# PJ_GRA_F.net
KiCad netlist of a schematic drawn in Altium Designer
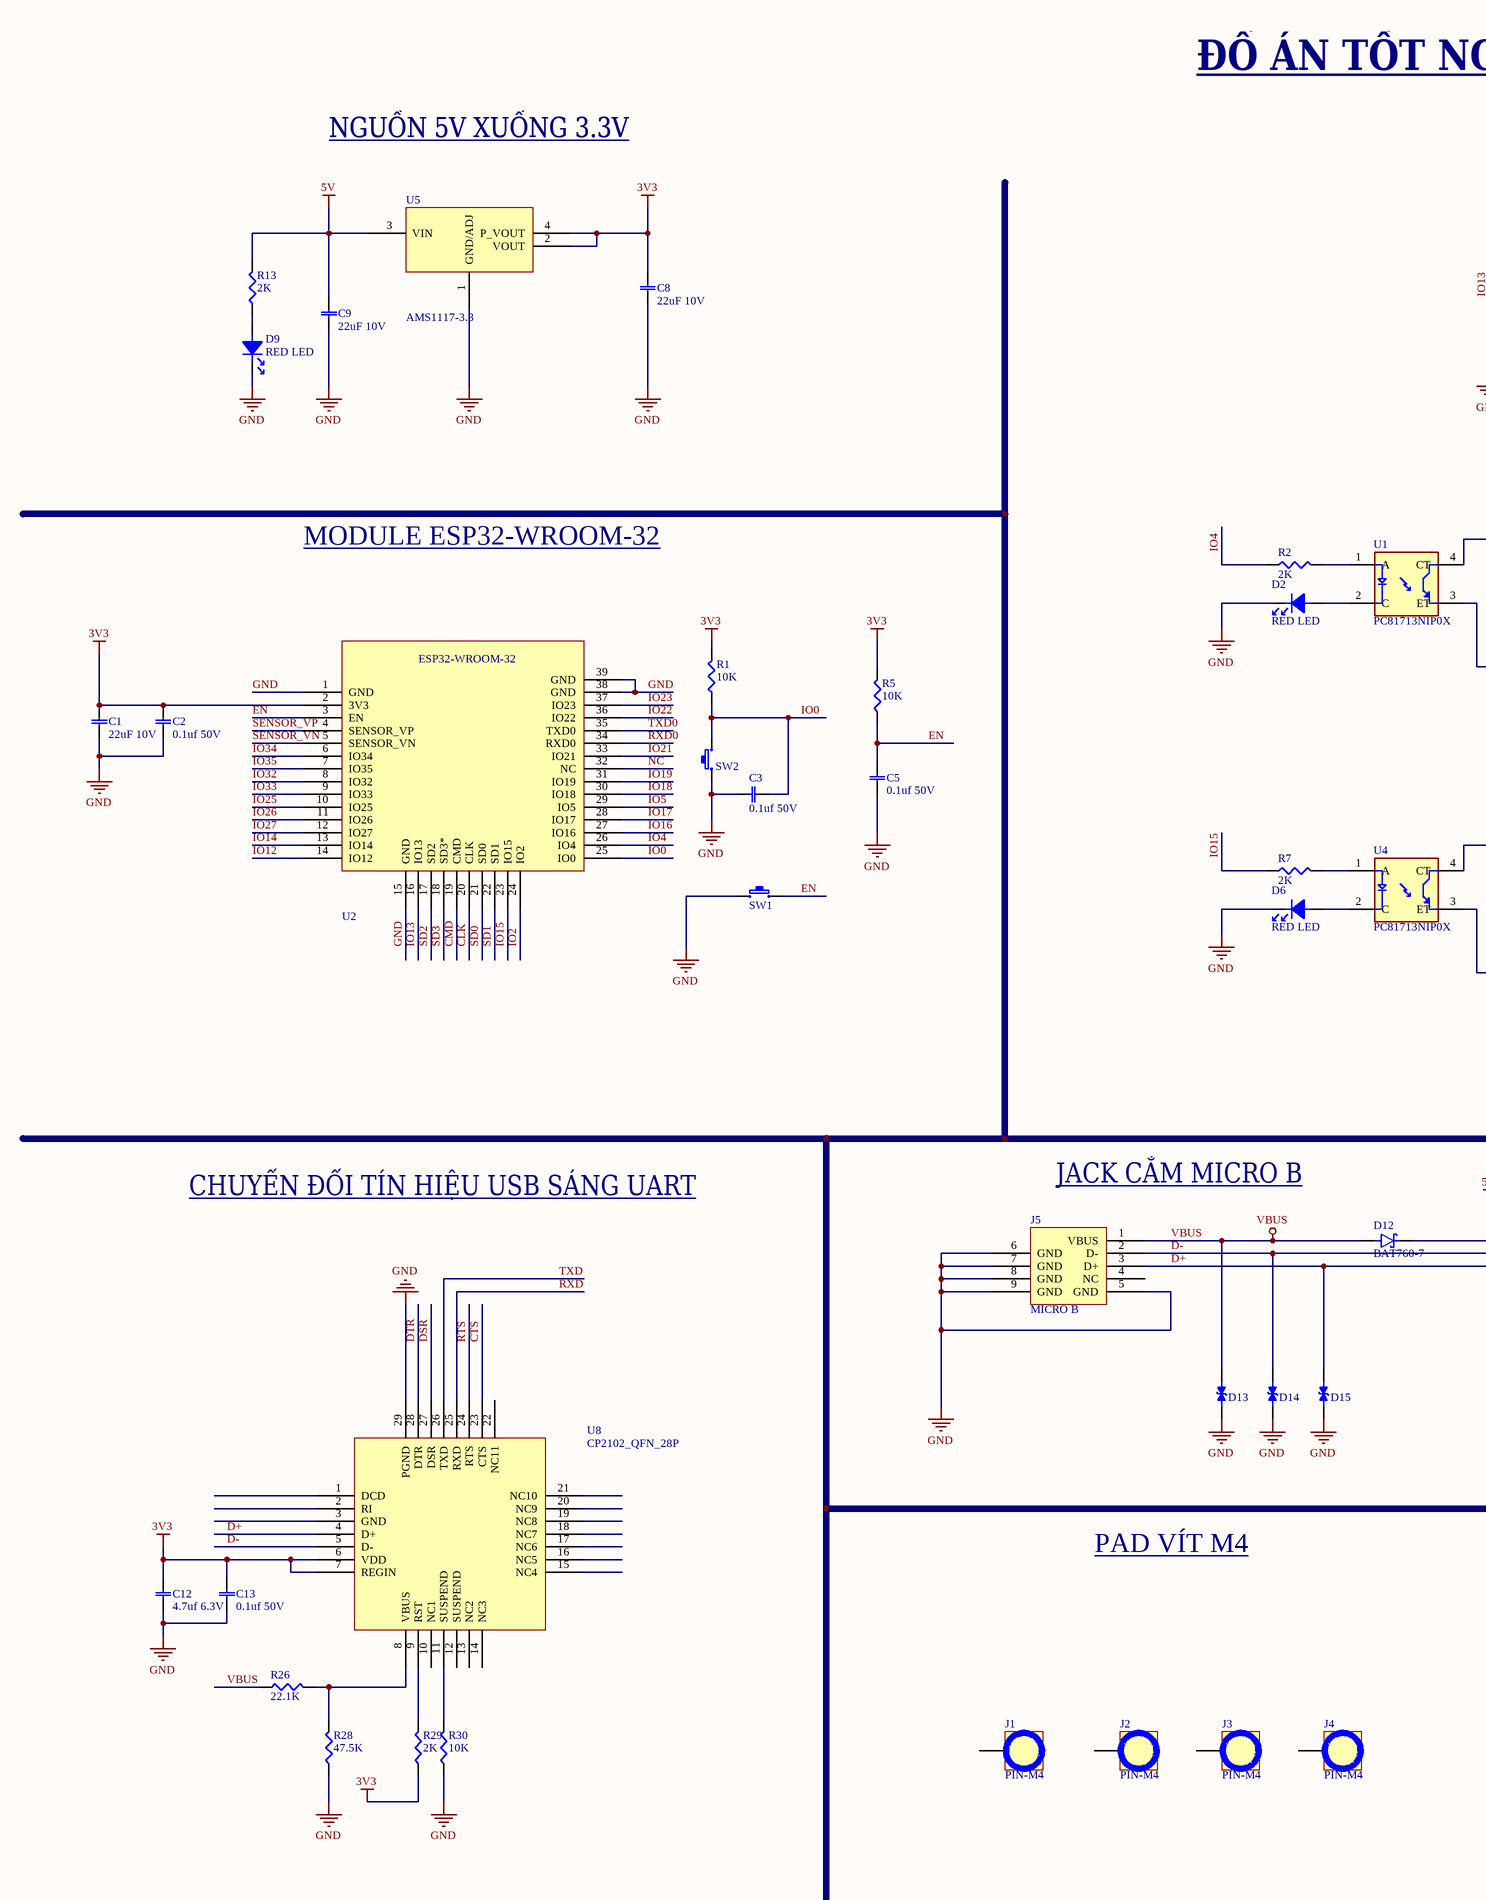
[diagram p0: PJ_GRA_F.SchDoc, left]
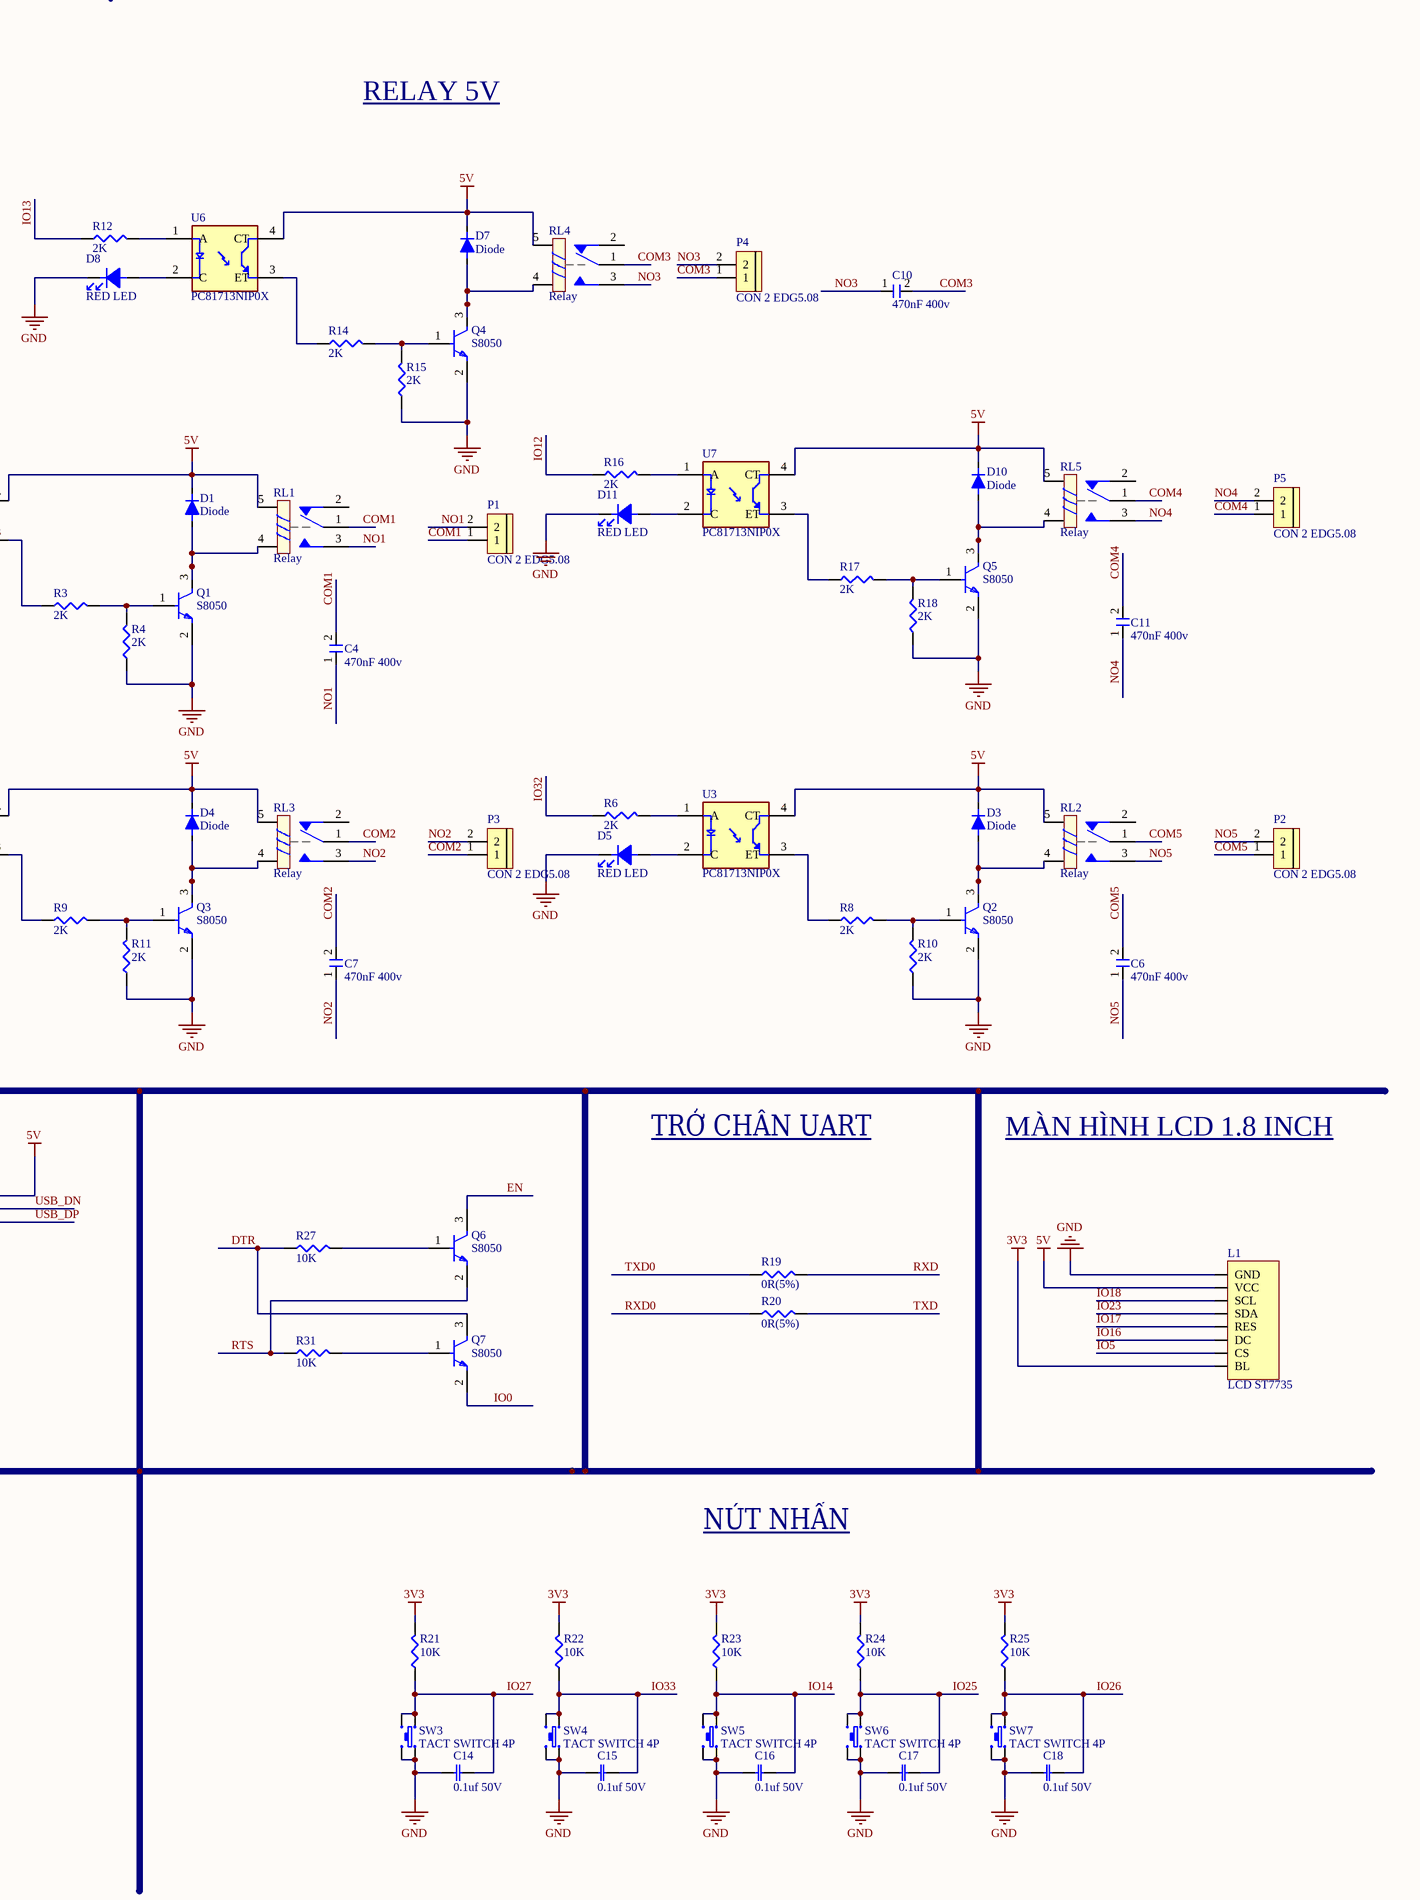
[diagram p1: PJ_GRA_F.SchDoc, right]

(export (version "E")
  (design (tool "Eeschema 10.0.6"))
  (components
    (comp (ref "C1")
      (value "22uF 10V")
      (footprint "FP-GRM188-0_2-IPC_A")
      (description "CAP CER 22UF 6.3V X5R 0603")
      (fields
        (field (name "MANUFACTURER") "Murata")
        (field (name "MANUFACTURER PART NUMBER") "GRM188R60J226MEA0J")
      )
      (libsource (lib "PJ_GRA_F") (part "GRM188R60J226MEA0J"))
    )
    (comp (ref "C2")
      (value "0.1uf 50V")
      (footprint "FP-C1005-050-0_05-IPC_A")
      (description "CAP CER 0.1UF 50V X7R 0402")
      (fields
        (field (name "MANUFACTURER") "TDK")
        (field (name "MANUFACTURER PART NUMBER") "C1005X7R1H104K050BB")
      )
      (libsource (lib "PJ_GRA_F") (part "C1005X7R1H104K050BB"))
    )
    (comp (ref "C3")
      (value "0.1uf 50V")
      (footprint "FP-C1005-050-0_05-IPC_A")
      (description "CAP CER 0.1UF 50V X7R 0402")
      (fields
        (field (name "MANUFACTURER") "TDK")
        (field (name "MANUFACTURER PART NUMBER") "C1005X7R1H104K050BB")
      )
      (libsource (lib "PJ_GRA_F") (part "C1005X7R1H104K050BB"))
    )
    (comp (ref "C4")
      (value "470nF 400v")
      (footprint "CAPRR750W80L1900T780H2200")
      (description "CAP 470nF 400V TH")
      (fields (field (name "MP") "ECQE4474RJT"))
      (libsource (lib "PJ_GRA_F") (part "470NF"))
    )
    (comp (ref "C5")
      (value "0.1uf 50V")
      (footprint "FP-C1005-050-0_05-IPC_A")
      (description "CAP CER 0.1UF 50V X7R 0402")
      (fields
        (field (name "MANUFACTURER") "TDK")
        (field (name "MANUFACTURER PART NUMBER") "C1005X7R1H104K050BB")
      )
      (libsource (lib "PJ_GRA_F") (part "C1005X7R1H104K050BB"))
    )
    (comp (ref "C6")
      (value "470nF 400v")
      (footprint "CAPRR750W80L1900T780H2200")
      (description "CAP 470nF 400V TH")
      (fields (field (name "MP") "ECQE4474RJT"))
      (libsource (lib "PJ_GRA_F") (part "470NF"))
    )
    (comp (ref "C7")
      (value "470nF 400v")
      (footprint "CAPRR750W80L1900T780H2200")
      (description "CAP 470nF 400V TH")
      (fields (field (name "MP") "ECQE4474RJT"))
      (libsource (lib "PJ_GRA_F") (part "470NF"))
    )
    (comp (ref "C8")
      (value "22uF 10V")
      (footprint "FP-GRM188-0_2-IPC_A")
      (description "CAP CER 22UF 6.3V X5R 0603")
      (fields
        (field (name "MANUFACTURER") "Murata")
        (field (name "MANUFACTURER PART NUMBER") "GRM188R60J226MEA0J")
      )
      (libsource (lib "PJ_GRA_F") (part "GRM188R60J226MEA0J"))
    )
    (comp (ref "C9")
      (value "22uF 10V")
      (footprint "FP-GRM188-0_2-IPC_A")
      (description "CAP CER 22UF 6.3V X5R 0603")
      (fields
        (field (name "MANUFACTURER") "Murata")
        (field (name "MANUFACTURER PART NUMBER") "GRM188R60J226MEA0J")
      )
      (libsource (lib "PJ_GRA_F") (part "GRM188R60J226MEA0J"))
    )
    (comp (ref "C10")
      (value "470nF 400v")
      (footprint "CAPRR750W80L1900T780H2200")
      (description "CAP 470nF 400V TH")
      (fields (field (name "MP") "ECQE4474RJT"))
      (libsource (lib "PJ_GRA_F") (part "470NF"))
    )
    (comp (ref "C11")
      (value "470nF 400v")
      (footprint "CAPRR750W80L1900T780H2200")
      (description "CAP 470nF 400V TH")
      (fields (field (name "MP") "ECQE4474RJT"))
      (libsource (lib "PJ_GRA_F") (part "470NF"))
    )
    (comp (ref "C12")
      (value "4.7uf 6.3V")
      (footprint "FP-C1005-050-0_05-IPC_A")
      (description "CAP CER 4.7UF 6.3V X5R 0402")
      (fields
        (field (name "MANUFACTURER") "Samsung")
        (field (name "MANUFACTURER PART NUMBER") "CL05A475KQ5NRNC")
      )
      (libsource (lib "PJ_GRA_F") (part "CL05A475KQ5NRNC"))
    )
    (comp (ref "C13")
      (value "0.1uf 50V")
      (footprint "FP-C1005-050-0_05-IPC_A")
      (description "CAP CER 0.1UF 50V X7R 0402")
      (fields
        (field (name "MANUFACTURER") "TDK")
        (field (name "MANUFACTURER PART NUMBER") "C1005X7R1H104K050BB")
      )
      (libsource (lib "PJ_GRA_F") (part "C1005X7R1H104K050BB"))
    )
    (comp (ref "C14")
      (value "0.1uf 50V")
      (footprint "FP-C1005-050-0_05-IPC_A")
      (description "CAP CER 0.1UF 50V X7R 0402")
      (fields
        (field (name "MANUFACTURER") "TDK")
        (field (name "MANUFACTURER PART NUMBER") "C1005X7R1H104K050BB")
      )
      (libsource (lib "PJ_GRA_F") (part "C1005X7R1H104K050BB"))
    )
    (comp (ref "C15")
      (value "0.1uf 50V")
      (footprint "FP-C1005-050-0_05-IPC_A")
      (description "CAP CER 0.1UF 50V X7R 0402")
      (fields
        (field (name "MANUFACTURER") "TDK")
        (field (name "MANUFACTURER PART NUMBER") "C1005X7R1H104K050BB")
      )
      (libsource (lib "PJ_GRA_F") (part "C1005X7R1H104K050BB"))
    )
    (comp (ref "C16")
      (value "0.1uf 50V")
      (footprint "FP-C1005-050-0_05-IPC_A")
      (description "CAP CER 0.1UF 50V X7R 0402")
      (fields
        (field (name "MANUFACTURER") "TDK")
        (field (name "MANUFACTURER PART NUMBER") "C1005X7R1H104K050BB")
      )
      (libsource (lib "PJ_GRA_F") (part "C1005X7R1H104K050BB"))
    )
    (comp (ref "C17")
      (value "0.1uf 50V")
      (footprint "FP-C1005-050-0_05-IPC_A")
      (description "CAP CER 0.1UF 50V X7R 0402")
      (fields
        (field (name "MANUFACTURER") "TDK")
        (field (name "MANUFACTURER PART NUMBER") "C1005X7R1H104K050BB")
      )
      (libsource (lib "PJ_GRA_F") (part "C1005X7R1H104K050BB"))
    )
    (comp (ref "C18")
      (value "0.1uf 50V")
      (footprint "FP-C1005-050-0_05-IPC_A")
      (description "CAP CER 0.1UF 50V X7R 0402")
      (fields
        (field (name "MANUFACTURER") "TDK")
        (field (name "MANUFACTURER PART NUMBER") "C1005X7R1H104K050BB")
      )
      (libsource (lib "PJ_GRA_F") (part "C1005X7R1H104K050BB"))
    )
    (comp (ref "D1")
      (value "Diode")
      (footprint "DO-214AC_SMA")
      (description "DO-214AC/SMA, 1000V, 1.00A")
      (fields (field (name "MANUFACTURER") "Diotec") (field (name "MANUFACTURER PART NUMBER") "M7"))
      (libsource (lib "PJ_GRA_F") (part "M7"))
    )
    (comp (ref "D2")
      (value "RED LED")
      (footprint "FP-6_541-5092_01-4-MFG")
      (description "LED RED 0603 SMD")
      (fields
        (field (name "MANUFACTURER") "Vishay Semiconductors")
        (field (name "MANUFACTURER PART NUMBER") "VLMS1300-GS08")
      )
      (libsource (lib "PJ_GRA_F") (part "VLMS1300-GS08"))
    )
    (comp (ref "D3")
      (value "Diode")
      (footprint "DO-214AC_SMA")
      (description "DO-214AC/SMA, 1000V, 1.00A")
      (fields (field (name "MANUFACTURER") "Diotec") (field (name "MANUFACTURER PART NUMBER") "M7"))
      (libsource (lib "PJ_GRA_F") (part "M7"))
    )
    (comp (ref "D4")
      (value "Diode")
      (footprint "DO-214AC_SMA")
      (description "DO-214AC/SMA, 1000V, 1.00A")
      (fields (field (name "MANUFACTURER") "Diotec") (field (name "MANUFACTURER PART NUMBER") "M7"))
      (libsource (lib "PJ_GRA_F") (part "M7"))
    )
    (comp (ref "D5")
      (value "RED LED")
      (footprint "FP-6_541-5092_01-4-MFG")
      (description "LED RED 0603 SMD")
      (fields
        (field (name "MANUFACTURER") "Vishay Semiconductors")
        (field (name "MANUFACTURER PART NUMBER") "VLMS1300-GS08")
      )
      (libsource (lib "PJ_GRA_F") (part "VLMS1300-GS08"))
    )
    (comp (ref "D6")
      (value "RED LED")
      (footprint "FP-6_541-5092_01-4-MFG")
      (description "LED RED 0603 SMD")
      (fields
        (field (name "MANUFACTURER") "Vishay Semiconductors")
        (field (name "MANUFACTURER PART NUMBER") "VLMS1300-GS08")
      )
      (libsource (lib "PJ_GRA_F") (part "VLMS1300-GS08"))
    )
    (comp (ref "D7")
      (value "Diode")
      (footprint "DO-214AC_SMA")
      (description "DO-214AC/SMA, 1000V, 1.00A")
      (fields (field (name "MANUFACTURER") "Diotec") (field (name "MANUFACTURER PART NUMBER") "M7"))
      (libsource (lib "PJ_GRA_F") (part "M7"))
    )
    (comp (ref "D8")
      (value "RED LED")
      (footprint "FP-6_541-5092_01-4-MFG")
      (description "LED RED 0603 SMD")
      (fields
        (field (name "MANUFACTURER") "Vishay Semiconductors")
        (field (name "MANUFACTURER PART NUMBER") "VLMS1300-GS08")
      )
      (libsource (lib "PJ_GRA_F") (part "VLMS1300-GS08"))
    )
    (comp (ref "D9")
      (value "RED LED")
      (footprint "FP-6_541-5092_01-4-MFG")
      (description "LED RED 0603 SMD")
      (fields
        (field (name "MANUFACTURER") "Vishay Semiconductors")
        (field (name "MANUFACTURER PART NUMBER") "VLMS1300-GS08")
      )
      (libsource (lib "PJ_GRA_F") (part "VLMS1300-GS08"))
    )
    (comp (ref "D10")
      (value "Diode")
      (footprint "DO-214AC_SMA")
      (description "DO-214AC/SMA, 1000V, 1.00A")
      (fields (field (name "MANUFACTURER") "Diotec") (field (name "MANUFACTURER PART NUMBER") "M7"))
      (libsource (lib "PJ_GRA_F") (part "M7"))
    )
    (comp (ref "D11")
      (value "RED LED")
      (footprint "FP-6_541-5092_01-4-MFG")
      (description "LED RED 0603 SMD")
      (fields
        (field (name "MANUFACTURER") "Vishay Semiconductors")
        (field (name "MANUFACTURER PART NUMBER") "VLMS1300-GS08")
      )
      (libsource (lib "PJ_GRA_F") (part "VLMS1300-GS08"))
    )
    (comp (ref "D12")
      (value "BAT760-7")
      (footprint "SOD2513X120N")
      (description "Schottky Diode,Vrrm=30V, Vr=21V, I=1A, IFSM=5.5A")
      (fields (field (name "MANUFACTURER") "Diodes") (field (name "LCSC PART NUMBER") "C124187"))
      (libsource (lib "PJ_GRA_F") (part "BAT760-7"))
    )
    (comp (ref "D13")
      (value "DIODE")
      (footprint "TVS_LESD5D5.0CT1G")
      (description "TVS DIODE 5.3VWM 12VC SOD882")
      (fields
        (field (name "MANUFACTURER") "Littelfuse")
        (field (name "MANUFACTURER PART NUMBER") "AQ3045-01ETG")
      )
      (libsource (lib "PJ_GRA_F") (part "AQ3045-01ETG"))
    )
    (comp (ref "D14")
      (value "DIODE")
      (footprint "TVS_LESD5D5.0CT1G")
      (description "TVS DIODE 5.3VWM 12VC SOD882")
      (fields
        (field (name "MANUFACTURER") "Littelfuse")
        (field (name "MANUFACTURER PART NUMBER") "AQ3045-01ETG")
      )
      (libsource (lib "PJ_GRA_F") (part "AQ3045-01ETG"))
    )
    (comp (ref "D15")
      (value "DIODE")
      (footprint "TVS_LESD5D5.0CT1G")
      (description "TVS DIODE 5.3VWM 12VC SOD882")
      (fields
        (field (name "MANUFACTURER") "Littelfuse")
        (field (name "MANUFACTURER PART NUMBER") "AQ3045-01ETG")
      )
      (libsource (lib "PJ_GRA_F") (part "AQ3045-01ETG"))
    )
    (comp (ref "J1") (value "PIN-M4") (footprint "M4") (libsource (lib "PJ_GRA_F") (part "PIN-M4")))
    (comp (ref "J2") (value "PIN-M4") (footprint "M4") (libsource (lib "PJ_GRA_F") (part "PIN-M4")))
    (comp (ref "J3") (value "PIN-M4") (footprint "M4") (libsource (lib "PJ_GRA_F") (part "PIN-M4")))
    (comp (ref "J4") (value "PIN-M4") (footprint "M4") (libsource (lib "PJ_GRA_F") (part "PIN-M4")))
    (comp (ref "J5")
      (value "MICRO B")
      (footprint "HRS_ZX62D-B-5P8")
      (description "USB 2.0 1.8A 1 Surface Mount，Right Angle 5P Female -30℃~+80℃ Micro-B SMD USB Connectors ROHS")
      (fields (field (name "LCSC PART NUMBER") "C668587"))
      (libsource (lib "PJ_GRA_F") (part "USB MICRO B 5 PIN"))
    )
    (comp (ref "L1")
      (value "LCD ST7735")
      (footprint "ST7735 (OLED -1.8 inch)")
      (description "32RGB x 162dot 262K Color with Frame Memory Single-Chip TFT Controller/Driver")
      (libsource (lib "PJ_GRA_F") (part "ST7735 (OLED -1.8 inch)"))
    )
    (comp (ref "P1")
      (value "CON 2 EDG5.08")
      (footprint "CON 2 2EDG5.08")
      (description "Cắm")
      (libsource (lib "Altium_Lib_by_KhueNguyenCreator") (part "CON 2 EDG5.08"))
    )
    (comp (ref "P2")
      (value "CON 2 EDG5.08")
      (footprint "CON 2 2EDG5.08")
      (description "Cắm")
      (libsource (lib "Altium_Lib_by_KhueNguyenCreator") (part "CON 2 EDG5.08"))
    )
    (comp (ref "P3")
      (value "CON 2 EDG5.08")
      (footprint "CON 2 2EDG5.08")
      (description "Cắm")
      (libsource (lib "Altium_Lib_by_KhueNguyenCreator") (part "CON 2 EDG5.08"))
    )
    (comp (ref "P4")
      (value "CON 2 EDG5.08")
      (footprint "CON 2 2EDG5.08")
      (description "Cắm")
      (libsource (lib "Altium_Lib_by_KhueNguyenCreator") (part "CON 2 EDG5.08"))
    )
    (comp (ref "P5")
      (value "CON 2 EDG5.08")
      (footprint "CON 2 2EDG5.08")
      (description "Cắm")
      (libsource (lib "Altium_Lib_by_KhueNguyenCreator") (part "CON 2 EDG5.08"))
    )
    (comp (ref "Q1")
      (value "S8050")
      (footprint "FP-SS8050-G-IPC_C")
      (description "TRANS NPN 25V 1.5A SOT23-3")
      (fields (field (name "MANUFACTURER") "Comchip") (field (name "MANUFACTURER PART NUMBER") "SS8050-G"))
      (libsource (lib "PJ_GRA_F") (part "SS8050-G"))
    )
    (comp (ref "Q2")
      (value "S8050")
      (footprint "FP-SS8050-G-IPC_C")
      (description "TRANS NPN 25V 1.5A SOT23-3")
      (fields (field (name "MANUFACTURER") "Comchip") (field (name "MANUFACTURER PART NUMBER") "SS8050-G"))
      (libsource (lib "PJ_GRA_F") (part "SS8050-G"))
    )
    (comp (ref "Q3")
      (value "S8050")
      (footprint "FP-SS8050-G-IPC_C")
      (description "TRANS NPN 25V 1.5A SOT23-3")
      (fields (field (name "MANUFACTURER") "Comchip") (field (name "MANUFACTURER PART NUMBER") "SS8050-G"))
      (libsource (lib "PJ_GRA_F") (part "SS8050-G"))
    )
    (comp (ref "Q4")
      (value "S8050")
      (footprint "FP-SS8050-G-IPC_C")
      (description "TRANS NPN 25V 1.5A SOT23-3")
      (fields (field (name "MANUFACTURER") "Comchip") (field (name "MANUFACTURER PART NUMBER") "SS8050-G"))
      (libsource (lib "PJ_GRA_F") (part "SS8050-G"))
    )
    (comp (ref "Q5")
      (value "S8050")
      (footprint "FP-SS8050-G-IPC_C")
      (description "TRANS NPN 25V 1.5A SOT23-3")
      (fields (field (name "MANUFACTURER") "Comchip") (field (name "MANUFACTURER PART NUMBER") "SS8050-G"))
      (libsource (lib "PJ_GRA_F") (part "SS8050-G"))
    )
    (comp (ref "Q6")
      (value "S8050")
      (footprint "FP-SS8050-G-IPC_C")
      (description "TRANS NPN 25V 1.5A SOT23-3")
      (fields (field (name "MANUFACTURER") "Comchip") (field (name "MANUFACTURER PART NUMBER") "SS8050-G"))
      (libsource (lib "PJ_GRA_F") (part "SS8050-G"))
    )
    (comp (ref "Q7")
      (value "S8050")
      (footprint "FP-SS8050-G-IPC_C")
      (description "TRANS NPN 25V 1.5A SOT23-3")
      (fields (field (name "MANUFACTURER") "Comchip") (field (name "MANUFACTURER PART NUMBER") "SS8050-G"))
      (libsource (lib "PJ_GRA_F") (part "SS8050-G"))
    )
    (comp (ref "R1")
      (value "10K")
      (footprint "FP-AC0402-IPC_A")
      (description "RES SMD 10K OHM 1% 1/16W 0402")
      (fields
        (field (name "MANUFACTURER") "Yageo")
        (field (name "MANUFACTURER PART NUMBER") "AC0402FR-0710KL")
      )
      (libsource (lib "PJ_GRA_F") (part "AC0402FR-0710KL"))
    )
    (comp (ref "R2")
      (value "2K")
      (footprint "FP-AC0402-IPC_A")
      (description "RES SMD 2K OHM 1% 1/16W 0402")
      (fields
        (field (name "MANUFACTURER") "Yageo")
        (field (name "MANUFACTURER PART NUMBER") "AC0402FR-072KL")
      )
      (libsource (lib "PJ_GRA_F") (part "AC0402FR-072KL"))
    )
    (comp (ref "R3")
      (value "2K")
      (footprint "FP-AC0402-IPC_A")
      (description "RES SMD 2K OHM 1% 1/16W 0402")
      (fields
        (field (name "MANUFACTURER") "Yageo")
        (field (name "MANUFACTURER PART NUMBER") "AC0402FR-072KL")
      )
      (libsource (lib "PJ_GRA_F") (part "AC0402FR-072KL"))
    )
    (comp (ref "R4")
      (value "2K")
      (footprint "FP-AC0402-IPC_A")
      (description "RES SMD 2K OHM 1% 1/16W 0402")
      (fields
        (field (name "MANUFACTURER") "Yageo")
        (field (name "MANUFACTURER PART NUMBER") "AC0402FR-072KL")
      )
      (libsource (lib "PJ_GRA_F") (part "AC0402FR-072KL"))
    )
    (comp (ref "R5")
      (value "10K")
      (footprint "FP-AC0402-IPC_A")
      (description "RES SMD 10K OHM 1% 1/16W 0402")
      (fields
        (field (name "MANUFACTURER") "Yageo")
        (field (name "MANUFACTURER PART NUMBER") "AC0402FR-0710KL")
      )
      (libsource (lib "PJ_GRA_F") (part "AC0402FR-0710KL"))
    )
    (comp (ref "R6")
      (value "2K")
      (footprint "FP-AC0402-IPC_A")
      (description "RES SMD 2K OHM 1% 1/16W 0402")
      (fields
        (field (name "MANUFACTURER") "Yageo")
        (field (name "MANUFACTURER PART NUMBER") "AC0402FR-072KL")
      )
      (libsource (lib "PJ_GRA_F") (part "AC0402FR-072KL"))
    )
    (comp (ref "R7")
      (value "2K")
      (footprint "FP-AC0402-IPC_A")
      (description "RES SMD 2K OHM 1% 1/16W 0402")
      (fields
        (field (name "MANUFACTURER") "Yageo")
        (field (name "MANUFACTURER PART NUMBER") "AC0402FR-072KL")
      )
      (libsource (lib "PJ_GRA_F") (part "AC0402FR-072KL"))
    )
    (comp (ref "R8")
      (value "2K")
      (footprint "FP-AC0402-IPC_A")
      (description "RES SMD 2K OHM 1% 1/16W 0402")
      (fields
        (field (name "MANUFACTURER") "Yageo")
        (field (name "MANUFACTURER PART NUMBER") "AC0402FR-072KL")
      )
      (libsource (lib "PJ_GRA_F") (part "AC0402FR-072KL"))
    )
    (comp (ref "R9")
      (value "2K")
      (footprint "FP-AC0402-IPC_A")
      (description "RES SMD 2K OHM 1% 1/16W 0402")
      (fields
        (field (name "MANUFACTURER") "Yageo")
        (field (name "MANUFACTURER PART NUMBER") "AC0402FR-072KL")
      )
      (libsource (lib "PJ_GRA_F") (part "AC0402FR-072KL"))
    )
    (comp (ref "R10")
      (value "2K")
      (footprint "FP-AC0402-IPC_A")
      (description "RES SMD 2K OHM 1% 1/16W 0402")
      (fields
        (field (name "MANUFACTURER") "Yageo")
        (field (name "MANUFACTURER PART NUMBER") "AC0402FR-072KL")
      )
      (libsource (lib "PJ_GRA_F") (part "AC0402FR-072KL"))
    )
    (comp (ref "R11")
      (value "2K")
      (footprint "FP-AC0402-IPC_A")
      (description "RES SMD 2K OHM 1% 1/16W 0402")
      (fields
        (field (name "MANUFACTURER") "Yageo")
        (field (name "MANUFACTURER PART NUMBER") "AC0402FR-072KL")
      )
      (libsource (lib "PJ_GRA_F") (part "AC0402FR-072KL"))
    )
    (comp (ref "R12")
      (value "2K")
      (footprint "FP-AC0402-IPC_A")
      (description "RES SMD 2K OHM 1% 1/16W 0402")
      (fields
        (field (name "MANUFACTURER") "Yageo")
        (field (name "MANUFACTURER PART NUMBER") "AC0402FR-072KL")
      )
      (libsource (lib "PJ_GRA_F") (part "AC0402FR-072KL"))
    )
    (comp (ref "R13")
      (value "2K")
      (footprint "FP-AC0402-IPC_A")
      (description "RES SMD 2K OHM 1% 1/16W 0402")
      (fields
        (field (name "MANUFACTURER") "Yageo")
        (field (name "MANUFACTURER PART NUMBER") "AC0402FR-072KL")
      )
      (libsource (lib "PJ_GRA_F") (part "AC0402FR-072KL"))
    )
    (comp (ref "R14")
      (value "2K")
      (footprint "FP-AC0402-IPC_A")
      (description "RES SMD 2K OHM 1% 1/16W 0402")
      (fields
        (field (name "MANUFACTURER") "Yageo")
        (field (name "MANUFACTURER PART NUMBER") "AC0402FR-072KL")
      )
      (libsource (lib "PJ_GRA_F") (part "AC0402FR-072KL"))
    )
    (comp (ref "R15")
      (value "2K")
      (footprint "FP-AC0402-IPC_A")
      (description "RES SMD 2K OHM 1% 1/16W 0402")
      (fields
        (field (name "MANUFACTURER") "Yageo")
        (field (name "MANUFACTURER PART NUMBER") "AC0402FR-072KL")
      )
      (libsource (lib "PJ_GRA_F") (part "AC0402FR-072KL"))
    )
    (comp (ref "R16")
      (value "2K")
      (footprint "FP-AC0402-IPC_A")
      (description "RES SMD 2K OHM 1% 1/16W 0402")
      (fields
        (field (name "MANUFACTURER") "Yageo")
        (field (name "MANUFACTURER PART NUMBER") "AC0402FR-072KL")
      )
      (libsource (lib "PJ_GRA_F") (part "AC0402FR-072KL"))
    )
    (comp (ref "R17")
      (value "2K")
      (footprint "FP-AC0402-IPC_A")
      (description "RES SMD 2K OHM 1% 1/16W 0402")
      (fields
        (field (name "MANUFACTURER") "Yageo")
        (field (name "MANUFACTURER PART NUMBER") "AC0402FR-072KL")
      )
      (libsource (lib "PJ_GRA_F") (part "AC0402FR-072KL"))
    )
    (comp (ref "R18")
      (value "2K")
      (footprint "FP-AC0402-IPC_A")
      (description "RES SMD 2K OHM 1% 1/16W 0402")
      (fields
        (field (name "MANUFACTURER") "Yageo")
        (field (name "MANUFACTURER PART NUMBER") "AC0402FR-072KL")
      )
      (libsource (lib "PJ_GRA_F") (part "AC0402FR-072KL"))
    )
    (comp (ref "R19")
      (value "0R(5%)")
      (footprint "FP-AC0402-IPC_A")
      (description "GENERAL PURPOSE CHIP RESISTOR Metal Glaze/thick Film, 0.0625W, 0ohm, Surface Mount, 0402")
      (fields
        (field (name "MANUFACTURER") "Yageo")
        (field (name "MANUFACTURER PART NUMBER") "RC0402JR-070RL")
      )
      (libsource (lib "PJ_GRA_F") (part "RC0402JR-070RL"))
    )
    (comp (ref "R20")
      (value "0R(5%)")
      (footprint "FP-AC0402-IPC_A")
      (description "GENERAL PURPOSE CHIP RESISTOR Metal Glaze/thick Film, 0.0625W, 0ohm, Surface Mount, 0402")
      (fields
        (field (name "MANUFACTURER") "Yageo")
        (field (name "MANUFACTURER PART NUMBER") "RC0402JR-070RL")
      )
      (libsource (lib "PJ_GRA_F") (part "RC0402JR-070RL"))
    )
    (comp (ref "R21")
      (value "10K")
      (footprint "FP-AC0402-IPC_A")
      (description "RES SMD 10K OHM 1% 1/16W 0402")
      (fields
        (field (name "MANUFACTURER") "Yageo")
        (field (name "MANUFACTURER PART NUMBER") "AC0402FR-0710KL")
      )
      (libsource (lib "PJ_GRA_F") (part "AC0402FR-0710KL"))
    )
    (comp (ref "R22")
      (value "10K")
      (footprint "FP-AC0402-IPC_A")
      (description "RES SMD 10K OHM 1% 1/16W 0402")
      (fields
        (field (name "MANUFACTURER") "Yageo")
        (field (name "MANUFACTURER PART NUMBER") "AC0402FR-0710KL")
      )
      (libsource (lib "PJ_GRA_F") (part "AC0402FR-0710KL"))
    )
    (comp (ref "R23")
      (value "10K")
      (footprint "FP-AC0402-IPC_A")
      (description "RES SMD 10K OHM 1% 1/16W 0402")
      (fields
        (field (name "MANUFACTURER") "Yageo")
        (field (name "MANUFACTURER PART NUMBER") "AC0402FR-0710KL")
      )
      (libsource (lib "PJ_GRA_F") (part "AC0402FR-0710KL"))
    )
    (comp (ref "R24")
      (value "10K")
      (footprint "FP-AC0402-IPC_A")
      (description "RES SMD 10K OHM 1% 1/16W 0402")
      (fields
        (field (name "MANUFACTURER") "Yageo")
        (field (name "MANUFACTURER PART NUMBER") "AC0402FR-0710KL")
      )
      (libsource (lib "PJ_GRA_F") (part "AC0402FR-0710KL"))
    )
    (comp (ref "R25")
      (value "10K")
      (footprint "FP-AC0402-IPC_A")
      (description "RES SMD 10K OHM 1% 1/16W 0402")
      (fields
        (field (name "MANUFACTURER") "Yageo")
        (field (name "MANUFACTURER PART NUMBER") "AC0402FR-0710KL")
      )
      (libsource (lib "PJ_GRA_F") (part "AC0402FR-0710KL"))
    )
    (comp (ref "R26")
      (value "22.1K")
      (footprint "FP-AC0402-IPC_A")
      (description "RES 22.1K OHM 1% 1/16W 0402")
      (fields
        (field (name "MANUFACTURER") "Vishay")
        (field (name "MANUFACTURER PART NUMBER") "CRCW040222K1FKED")
      )
      (libsource (lib "PJ_GRA_F") (part "CRCW040222K1FKED"))
    )
    (comp (ref "R27")
      (value "10K")
      (footprint "FP-AC0402-IPC_A")
      (description "RES SMD 10K OHM 1% 1/16W 0402")
      (fields
        (field (name "MANUFACTURER") "Yageo")
        (field (name "MANUFACTURER PART NUMBER") "AC0402FR-0710KL")
      )
      (libsource (lib "PJ_GRA_F") (part "AC0402FR-0710KL"))
    )
    (comp (ref "R28")
      (value "47.5K")
      (footprint "FP-AC0402-IPC_A")
      (description "RES 47.5K OHM 1% 1/16W 0402")
      (fields
        (field (name "MANUFACTURER") "Yageo")
        (field (name "MANUFACTURER PART NUMBER") "RC0402FR-0747K5L")
      )
      (libsource (lib "PJ_GRA_F") (part "RC0402FR-0747K5L"))
    )
    (comp (ref "R29")
      (value "2K")
      (footprint "FP-AC0402-IPC_A")
      (description "RES SMD 2K OHM 1% 1/16W 0402")
      (fields
        (field (name "MANUFACTURER") "Yageo")
        (field (name "MANUFACTURER PART NUMBER") "AC0402FR-072KL")
      )
      (libsource (lib "PJ_GRA_F") (part "AC0402FR-072KL"))
    )
    (comp (ref "R30")
      (value "10K")
      (footprint "FP-AC0402-IPC_A")
      (description "RES SMD 10K OHM 1% 1/16W 0402")
      (fields
        (field (name "MANUFACTURER") "Yageo")
        (field (name "MANUFACTURER PART NUMBER") "AC0402FR-0710KL")
      )
      (libsource (lib "PJ_GRA_F") (part "AC0402FR-0710KL"))
    )
    (comp (ref "R31")
      (value "10K")
      (footprint "FP-AC0402-IPC_A")
      (description "RES SMD 10K OHM 1% 1/16W 0402")
      (fields
        (field (name "MANUFACTURER") "Yageo")
        (field (name "MANUFACTURER PART NUMBER") "AC0402FR-0710KL")
      )
      (libsource (lib "PJ_GRA_F") (part "AC0402FR-0710KL"))
    )
    (comp (ref "RL1")
      (value "Relay")
      (footprint "Relay 5 Chan SRD")
      (description "Relay 5 Chan")
      (libsource (lib "Altium_Lib_by_KhueNguyenCreator") (part "Relay 5 Chan SRD"))
    )
    (comp (ref "RL2")
      (value "Relay")
      (footprint "Relay 5 Chan SRD")
      (description "Relay 5 Chan")
      (libsource (lib "Altium_Lib_by_KhueNguyenCreator") (part "Relay 5 Chan SRD"))
    )
    (comp (ref "RL3")
      (value "Relay")
      (footprint "Relay 5 Chan SRD")
      (description "Relay 5 Chan")
      (libsource (lib "Altium_Lib_by_KhueNguyenCreator") (part "Relay 5 Chan SRD"))
    )
    (comp (ref "RL4")
      (value "Relay")
      (footprint "Relay 5 Chan SRD")
      (description "Relay 5 Chan")
      (libsource (lib "Altium_Lib_by_KhueNguyenCreator") (part "Relay 5 Chan SRD"))
    )
    (comp (ref "RL5")
      (value "Relay")
      (footprint "Relay 5 Chan SRD")
      (description "Relay 5 Chan")
      (libsource (lib "Altium_Lib_by_KhueNguyenCreator") (part "Relay 5 Chan SRD"))
    )
    (comp (ref "SW1")
      (value "Tact Switch")
      (footprint "SKRK")
      (description "reset button, 2-pin, 3x4x2, SMT")
      (libsource (lib "PJ_GRA_F") (part "Tact Switch  2P"))
    )
    (comp (ref "SW2")
      (value "Tact Switch")
      (footprint "SKRK")
      (description "reset button, 2-pin, 3x4x2, SMT")
      (libsource (lib "PJ_GRA_F") (part "Tact Switch  2P"))
    )
    (comp (ref "SW3")
      (value "TACT SWITCH 4P")
      (footprint "SW_B3F-4055")
      (description "12x12")
      (fields (field (name "MP") "B3F-4055"))
      (libsource (lib "PJ_GRA_F") (part "TACT SWITCH 4P"))
    )
    (comp (ref "SW4")
      (value "TACT SWITCH 4P")
      (footprint "SW_B3F-4055")
      (description "12x12")
      (fields (field (name "MP") "B3F-4055"))
      (libsource (lib "PJ_GRA_F") (part "TACT SWITCH 4P"))
    )
    (comp (ref "SW5")
      (value "TACT SWITCH 4P")
      (footprint "SW_B3F-4055")
      (description "12x12")
      (fields (field (name "MP") "B3F-4055"))
      (libsource (lib "PJ_GRA_F") (part "TACT SWITCH 4P"))
    )
    (comp (ref "SW6")
      (value "TACT SWITCH 4P")
      (footprint "SW_B3F-4055")
      (description "12x12")
      (fields (field (name "MP") "B3F-4055"))
      (libsource (lib "PJ_GRA_F") (part "TACT SWITCH 4P"))
    )
    (comp (ref "SW7")
      (value "TACT SWITCH 4P")
      (footprint "SW_B3F-4055")
      (description "12x12")
      (fields (field (name "MP") "B3F-4055"))
      (libsource (lib "PJ_GRA_F") (part "TACT SWITCH 4P"))
    )
    (comp (ref "U1")
      (value "PC81713NIP0X")
      (footprint "SOT254P1025X400-4N")
      (description "Optoisolator Transistor Output 5000Vrms 1 Channel 4-SMD")
      (fields (field (name "MF") "SHARP/Socle Technology"))
      (libsource (lib "PJ_GRA_F") (part "PC81713NIP0X"))
    )
    (comp (ref "U2")
      (value "ESP32-WROOM-32D-N4")
      (footprint "FP-ESP32-WROOM-32D_M113DH-0")
      (description "Wi-Fi/BT BLE Module ESP32-D0WD, SPI Flash, UART, PCB antenna")
      (fields (field (name "MANUFACTURER") "Espressif Systems") (field (name "LCSC PART NUMBER") "C473012"))
      (libsource (lib "PJ_GRA_F") (part "ESP32-WROOM-32D-N4"))
    )
    (comp (ref "U3")
      (value "PC81713NIP0X")
      (footprint "SOT254P1025X400-4N")
      (description "Optoisolator Transistor Output 5000Vrms 1 Channel 4-SMD")
      (fields (field (name "MF") "SHARP/Socle Technology"))
      (libsource (lib "PJ_GRA_F") (part "PC81713NIP0X"))
    )
    (comp (ref "U4")
      (value "PC81713NIP0X")
      (footprint "SOT254P1025X400-4N")
      (description "Optoisolator Transistor Output 5000Vrms 1 Channel 4-SMD")
      (fields (field (name "MF") "SHARP/Socle Technology"))
      (libsource (lib "PJ_GRA_F") (part "PC81713NIP0X"))
    )
    (comp (ref "U5")
      (value "AMS1117-3.3")
      (footprint "FP-AMS1117-IPC_A")
      (description "IC Ldo Reg 3.3V 1A SOT223")
      (fields (field (name "MANUFACTURER") "Revvo") (field (name "LCSC PART NUMBER") "C347222"))
      (libsource (lib "PJ_GRA_F") (part "AMS1117-3.3 (2)"))
    )
    (comp (ref "U6")
      (value "PC81713NIP0X")
      (footprint "SOT254P1025X400-4N")
      (description "Optoisolator Transistor Output 5000Vrms 1 Channel 4-SMD")
      (fields (field (name "MF") "SHARP/Socle Technology"))
      (libsource (lib "PJ_GRA_F") (part "PC81713NIP0X"))
    )
    (comp (ref "U7")
      (value "PC81713NIP0X")
      (footprint "SOT254P1025X400-4N")
      (description "Optoisolator Transistor Output 5000Vrms 1 Channel 4-SMD")
      (fields (field (name "MF") "SHARP/Socle Technology"))
      (libsource (lib "PJ_GRA_F") (part "PC81713NIP0X"))
    )
    (comp (ref "U8")
      (value "CP2102_QFN_28P")
      (footprint "FP-CP2102N-A01-GQFN28-IPC_A - duplicate")
      (description "USB-to-UART,USB2.0 full speed, data rate up to 3M baud")
      (fields (field (name "LCSC PART NUMBER") "C105167"))
      (libsource (lib "PJ_GRA_F") (part "CP2102N-A01-GQFN28"))
    )
  )
  (nets
    (net (code "1") (name "/CLK") (class "Default")
      (node (ref "U2") (pin "20") (pinfunction "CLK_20") (pintype "passive"))
    )
    (net (code "2") (name "/CMD") (class "Default")
      (node (ref "U2") (pin "19") (pinfunction "CMD_19") (pintype "passive"))
    )
    (net (code "3") (name "/COM1") (class "Default")
      (node (ref "C4") (pin "2") (pinfunction "2_2") (pintype "passive"))
      (node (ref "P1") (pin "1") (pinfunction "1_1") (pintype "passive"))
      (node (ref "RL1") (pin "1") (pinfunction "1_1") (pintype "passive"))
    )
    (net (code "4") (name "/COM2") (class "Default")
      (node (ref "C7") (pin "2") (pinfunction "2_2") (pintype "passive"))
      (node (ref "P3") (pin "1") (pinfunction "1_1") (pintype "passive"))
      (node (ref "RL3") (pin "1") (pinfunction "1_1") (pintype "passive"))
    )
    (net (code "5") (name "/COM3") (class "Default")
      (node (ref "C10") (pin "2") (pinfunction "2_2") (pintype "passive"))
      (node (ref "P4") (pin "1") (pinfunction "1_1") (pintype "passive"))
      (node (ref "RL4") (pin "1") (pinfunction "1_1") (pintype "passive"))
    )
    (net (code "6") (name "/COM4") (class "Default")
      (node (ref "C11") (pin "2") (pinfunction "2_2") (pintype "passive"))
      (node (ref "P5") (pin "1") (pinfunction "1_1") (pintype "passive"))
      (node (ref "RL5") (pin "1") (pinfunction "1_1") (pintype "passive"))
    )
    (net (code "7") (name "/COM5") (class "Default")
      (node (ref "C6") (pin "2") (pinfunction "2_2") (pintype "passive"))
      (node (ref "P2") (pin "1") (pinfunction "1_1") (pintype "passive"))
      (node (ref "RL2") (pin "1") (pinfunction "1_1") (pintype "passive"))
    )
    (net (code "8") (name "/CTS") (class "Default")
      (node (ref "U8") (pin "23") (pinfunction "CTS_23") (pintype "passive"))
    )
    (net (code "9") (name "/D+") (class "Default")
      (node (ref "D15") (pin "2") (pinfunction "2_2") (pintype "passive"))
      (node (ref "J5") (pin "3") (pinfunction "D+_3") (pintype "passive"))
      (node (ref "U8") (pin "4") (pinfunction "D+_4") (pintype "passive"))
    )
    (net (code "10") (name "/D-") (class "Default")
      (node (ref "D14") (pin "2") (pinfunction "2_2") (pintype "passive"))
      (node (ref "J5") (pin "2") (pinfunction "D-_2") (pintype "passive"))
      (node (ref "U8") (pin "5") (pinfunction "D-_5") (pintype "passive"))
    )
    (net (code "11") (name "/DSR") (class "Default")
      (node (ref "U8") (pin "27") (pinfunction "DSR_27") (pintype "passive"))
    )
    (net (code "12") (name "/DTR") (class "Default")
      (node (ref "Q7") (pin "3") (pinfunction "C_3") (pintype "passive"))
      (node (ref "R27") (pin "1") (pinfunction "1_1") (pintype "passive"))
      (node (ref "U8") (pin "28") (pinfunction "DTR_28") (pintype "passive"))
    )
    (net (code "13") (name "/EN") (class "Default")
      (node (ref "C5") (pin "2") (pinfunction "2_2") (pintype "passive"))
      (node (ref "Q6") (pin "3") (pinfunction "C_3") (pintype "passive"))
      (node (ref "R5") (pin "1") (pinfunction "1_1") (pintype "passive"))
      (node (ref "SW1") (pin "1") (pinfunction "1_1") (pintype "passive"))
      (node (ref "U2") (pin "3") (pinfunction "EN_3") (pintype "passive"))
    )
    (net (code "14") (name "/IO0") (class "Default")
      (node (ref "C3") (pin "2") (pinfunction "2_2") (pintype "passive"))
      (node (ref "Q7") (pin "2") (pinfunction "E_2") (pintype "passive"))
      (node (ref "R1") (pin "1") (pinfunction "1_1") (pintype "passive"))
      (node (ref "SW2") (pin "1") (pinfunction "1_1") (pintype "passive"))
      (node (ref "U2") (pin "25") (pinfunction "IO0_25") (pintype "passive"))
    )
    (net (code "15") (name "/IO2") (class "Default")
      (node (ref "U2") (pin "24") (pinfunction "IO2_24") (pintype "passive"))
    )
    (net (code "16") (name "/IO4") (class "Default")
      (node (ref "R2") (pin "1") (pinfunction "1_1") (pintype "passive"))
      (node (ref "U2") (pin "26") (pinfunction "IO4_26") (pintype "passive"))
    )
    (net (code "17") (name "/IO5") (class "Default")
      (node (ref "L1") (pin "7") (pinfunction "CS_7") (pintype "passive"))
      (node (ref "U2") (pin "29") (pinfunction "IO5_29") (pintype "passive"))
    )
    (net (code "18") (name "/IO12") (class "Default")
      (node (ref "R16") (pin "1") (pinfunction "1_1") (pintype "passive"))
      (node (ref "U2") (pin "14") (pinfunction "IO12_14") (pintype "passive"))
    )
    (net (code "19") (name "/IO13") (class "Default")
      (node (ref "R12") (pin "1") (pinfunction "1_1") (pintype "passive"))
      (node (ref "U2") (pin "16") (pinfunction "IO13_16") (pintype "passive"))
    )
    (net (code "20") (name "/IO14") (class "Default")
      (node (ref "C16") (pin "2") (pinfunction "2_2") (pintype "passive"))
      (node (ref "R23") (pin "1") (pinfunction "1_1") (pintype "passive"))
      (node (ref "SW5") (pin "1") (pinfunction "1_1") (pintype "passive"))
      (node (ref "SW5") (pin "3") (pinfunction "3_3") (pintype "passive"))
      (node (ref "U2") (pin "13") (pinfunction "IO14_13") (pintype "passive"))
    )
    (net (code "21") (name "/IO15") (class "Default")
      (node (ref "R7") (pin "1") (pinfunction "1_1") (pintype "passive"))
      (node (ref "U2") (pin "23") (pinfunction "IO15_23") (pintype "passive"))
    )
    (net (code "22") (name "/IO16") (class "Default")
      (node (ref "L1") (pin "6") (pinfunction "DC_6") (pintype "passive"))
      (node (ref "U2") (pin "27") (pinfunction "IO16_27") (pintype "passive"))
    )
    (net (code "23") (name "/IO17") (class "Default")
      (node (ref "L1") (pin "5") (pinfunction "RES_5") (pintype "passive"))
      (node (ref "U2") (pin "28") (pinfunction "IO17_28") (pintype "passive"))
    )
    (net (code "24") (name "/IO18") (class "Default")
      (node (ref "L1") (pin "3") (pinfunction "SCL_3") (pintype "passive"))
      (node (ref "U2") (pin "30") (pinfunction "IO18_30") (pintype "passive"))
    )
    (net (code "25") (name "/IO19") (class "Default")
      (node (ref "U2") (pin "31") (pinfunction "IO19_31") (pintype "passive"))
    )
    (net (code "26") (name "/IO21") (class "Default")
      (node (ref "U2") (pin "33") (pinfunction "IO21_33") (pintype "passive"))
    )
    (net (code "27") (name "/IO22") (class "Default")
      (node (ref "U2") (pin "36") (pinfunction "IO22_36") (pintype "passive"))
    )
    (net (code "28") (name "/IO23") (class "Default")
      (node (ref "L1") (pin "4") (pinfunction "SDA_4") (pintype "passive"))
      (node (ref "U2") (pin "37") (pinfunction "IO23_37") (pintype "passive"))
    )
    (net (code "29") (name "/IO25") (class "Default")
      (node (ref "C17") (pin "2") (pinfunction "2_2") (pintype "passive"))
      (node (ref "R24") (pin "1") (pinfunction "1_1") (pintype "passive"))
      (node (ref "SW6") (pin "1") (pinfunction "1_1") (pintype "passive"))
      (node (ref "SW6") (pin "3") (pinfunction "3_3") (pintype "passive"))
      (node (ref "U2") (pin "10") (pinfunction "IO25_10") (pintype "passive"))
    )
    (net (code "30") (name "/IO26") (class "Default")
      (node (ref "C18") (pin "2") (pinfunction "2_2") (pintype "passive"))
      (node (ref "R25") (pin "1") (pinfunction "1_1") (pintype "passive"))
      (node (ref "SW7") (pin "1") (pinfunction "1_1") (pintype "passive"))
      (node (ref "SW7") (pin "3") (pinfunction "3_3") (pintype "passive"))
      (node (ref "U2") (pin "11") (pinfunction "IO26_11") (pintype "passive"))
    )
    (net (code "31") (name "/IO27") (class "Default")
      (node (ref "C14") (pin "2") (pinfunction "2_2") (pintype "passive"))
      (node (ref "R21") (pin "1") (pinfunction "1_1") (pintype "passive"))
      (node (ref "SW3") (pin "1") (pinfunction "1_1") (pintype "passive"))
      (node (ref "SW3") (pin "3") (pinfunction "3_3") (pintype "passive"))
      (node (ref "U2") (pin "12") (pinfunction "IO27_12") (pintype "passive"))
    )
    (net (code "32") (name "/IO32") (class "Default")
      (node (ref "R6") (pin "1") (pinfunction "1_1") (pintype "passive"))
      (node (ref "U2") (pin "8") (pinfunction "IO32_8") (pintype "passive"))
    )
    (net (code "33") (name "/IO33") (class "Default")
      (node (ref "C15") (pin "2") (pinfunction "2_2") (pintype "passive"))
      (node (ref "R22") (pin "1") (pinfunction "1_1") (pintype "passive"))
      (node (ref "SW4") (pin "1") (pinfunction "1_1") (pintype "passive"))
      (node (ref "SW4") (pin "3") (pinfunction "3_3") (pintype "passive"))
      (node (ref "U2") (pin "9") (pinfunction "IO33_9") (pintype "passive"))
    )
    (net (code "34") (name "/IO34") (class "Default")
      (node (ref "U2") (pin "6") (pinfunction "IO34_6") (pintype "passive"))
    )
    (net (code "35") (name "/IO35") (class "Default")
      (node (ref "U2") (pin "7") (pinfunction "IO35_7") (pintype "passive"))
    )
    (net (code "36") (name "/NC") (class "Default")
      (node (ref "U2") (pin "32") (pinfunction "NC_32") (pintype "passive"))
    )
    (net (code "37") (name "/NO1") (class "Default")
      (node (ref "C4") (pin "1") (pinfunction "1_1") (pintype "passive"))
      (node (ref "P1") (pin "2") (pinfunction "2_2") (pintype "passive"))
      (node (ref "RL1") (pin "3") (pinfunction "3_3") (pintype "passive"))
    )
    (net (code "38") (name "/NO2") (class "Default")
      (node (ref "C7") (pin "1") (pinfunction "1_1") (pintype "passive"))
      (node (ref "P3") (pin "2") (pinfunction "2_2") (pintype "passive"))
      (node (ref "RL3") (pin "3") (pinfunction "3_3") (pintype "passive"))
    )
    (net (code "39") (name "/NO3") (class "Default")
      (node (ref "C10") (pin "1") (pinfunction "1_1") (pintype "passive"))
      (node (ref "P4") (pin "2") (pinfunction "2_2") (pintype "passive"))
      (node (ref "RL4") (pin "3") (pinfunction "3_3") (pintype "passive"))
    )
    (net (code "40") (name "/NO4") (class "Default")
      (node (ref "C11") (pin "1") (pinfunction "1_1") (pintype "passive"))
      (node (ref "P5") (pin "2") (pinfunction "2_2") (pintype "passive"))
      (node (ref "RL5") (pin "3") (pinfunction "3_3") (pintype "passive"))
    )
    (net (code "41") (name "/NO5") (class "Default")
      (node (ref "C6") (pin "1") (pinfunction "1_1") (pintype "passive"))
      (node (ref "P2") (pin "2") (pinfunction "2_2") (pintype "passive"))
      (node (ref "RL2") (pin "3") (pinfunction "3_3") (pintype "passive"))
    )
    (net (code "42") (name "/RTS") (class "Default")
      (node (ref "Q6") (pin "2") (pinfunction "E_2") (pintype "passive"))
      (node (ref "R31") (pin "1") (pinfunction "1_1") (pintype "passive"))
      (node (ref "U8") (pin "24") (pinfunction "RTS_24") (pintype "passive"))
    )
    (net (code "43") (name "/RXD") (class "Default")
      (node (ref "R19") (pin "2") (pinfunction "2_2") (pintype "passive"))
      (node (ref "U8") (pin "25") (pinfunction "RXD_25") (pintype "passive"))
    )
    (net (code "44") (name "/RXD0") (class "Default")
      (node (ref "R20") (pin "1") (pinfunction "1_1") (pintype "passive"))
      (node (ref "U2") (pin "34") (pinfunction "RXD0_34") (pintype "passive"))
    )
    (net (code "45") (name "/SD0") (class "Default")
      (node (ref "U2") (pin "21") (pinfunction "SD0_21") (pintype "passive"))
    )
    (net (code "46") (name "/SD1") (class "Default")
      (node (ref "U2") (pin "22") (pinfunction "SD1_22") (pintype "passive"))
    )
    (net (code "47") (name "/SD2") (class "Default")
      (node (ref "U2") (pin "17") (pinfunction "SD2_17") (pintype "passive"))
    )
    (net (code "48") (name "/SD3") (class "Default")
      (node (ref "U2") (pin "18") (pinfunction "SD3*_18") (pintype "passive"))
    )
    (net (code "49") (name "/SENSOR_VN") (class "Default")
      (node (ref "U2") (pin "5") (pinfunction "SENSOR_VN_5") (pintype "passive"))
    )
    (net (code "50") (name "/SENSOR_VP") (class "Default")
      (node (ref "U2") (pin "4") (pinfunction "SENSOR_VP_4") (pintype "passive"))
    )
    (net (code "51") (name "/TXD") (class "Default")
      (node (ref "R20") (pin "2") (pinfunction "2_2") (pintype "passive"))
      (node (ref "U8") (pin "26") (pinfunction "TXD_26") (pintype "passive"))
    )
    (net (code "52") (name "/TXD0") (class "Default")
      (node (ref "R19") (pin "1") (pinfunction "1_1") (pintype "passive"))
      (node (ref "U2") (pin "35") (pinfunction "TXD0_35") (pintype "passive"))
    )
    (net (code "53") (name "3V3") (class "Default")
      (node (ref "C1") (pin "2") (pinfunction "2_2") (pintype "passive"))
      (node (ref "C12") (pin "2") (pinfunction "2_2") (pintype "passive"))
      (node (ref "C13") (pin "2") (pinfunction "2_2") (pintype "passive"))
      (node (ref "C2") (pin "2") (pinfunction "2_2") (pintype "passive"))
      (node (ref "C8") (pin "2") (pinfunction "2_2") (pintype "passive"))
      (node (ref "L1") (pin "8") (pinfunction "BL_8") (pintype "passive"))
      (node (ref "R1") (pin "2") (pinfunction "2_2") (pintype "passive"))
      (node (ref "R21") (pin "2") (pinfunction "2_2") (pintype "passive"))
      (node (ref "R22") (pin "2") (pinfunction "2_2") (pintype "passive"))
      (node (ref "R23") (pin "2") (pinfunction "2_2") (pintype "passive"))
      (node (ref "R24") (pin "2") (pinfunction "2_2") (pintype "passive"))
      (node (ref "R25") (pin "2") (pinfunction "2_2") (pintype "passive"))
      (node (ref "R29") (pin "1") (pinfunction "1_1") (pintype "passive"))
      (node (ref "R5") (pin "2") (pinfunction "2_2") (pintype "passive"))
      (node (ref "U2") (pin "2") (pinfunction "3V3_2") (pintype "passive"))
      (node (ref "U5") (pin "2") (pinfunction "VOUT_2") (pintype "passive"))
      (node (ref "U5") (pin "4") (pinfunction "P_VOUT_4") (pintype "passive"))
      (node (ref "U8") (pin "6") (pinfunction "VDD_6") (pintype "passive"))
      (node (ref "U8") (pin "7") (pinfunction "REGIN_7") (pintype "passive"))
    )
    (net (code "54") (name "5V") (class "Default")
      (node (ref "C9") (pin "2") (pinfunction "2_2") (pintype "passive"))
      (node (ref "D1") (pin "K") (pinfunction "K_K") (pintype "passive"))
      (node (ref "D10") (pin "K") (pinfunction "K_K") (pintype "passive"))
      (node (ref "D12") (pin "C") (pinfunction "K_C") (pintype "passive"))
      (node (ref "D3") (pin "K") (pinfunction "K_K") (pintype "passive"))
      (node (ref "D4") (pin "K") (pinfunction "K_K") (pintype "passive"))
      (node (ref "D7") (pin "K") (pinfunction "K_K") (pintype "passive"))
      (node (ref "L1") (pin "2") (pinfunction "VCC_2") (pintype "passive"))
      (node (ref "R13") (pin "2") (pinfunction "2_2") (pintype "passive"))
      (node (ref "RL1") (pin "5") (pinfunction "5_5") (pintype "passive"))
      (node (ref "RL2") (pin "5") (pinfunction "5_5") (pintype "passive"))
      (node (ref "RL3") (pin "5") (pinfunction "5_5") (pintype "passive"))
      (node (ref "RL4") (pin "5") (pinfunction "5_5") (pintype "passive"))
      (node (ref "RL5") (pin "5") (pinfunction "5_5") (pintype "passive"))
      (node (ref "U1") (pin "4") (pinfunction "CT_4") (pintype "passive"))
      (node (ref "U3") (pin "4") (pinfunction "CT_4") (pintype "passive"))
      (node (ref "U4") (pin "4") (pinfunction "CT_4") (pintype "passive"))
      (node (ref "U5") (pin "3") (pinfunction "VIN_3") (pintype "passive"))
      (node (ref "U6") (pin "4") (pinfunction "CT_4") (pintype "passive"))
      (node (ref "U7") (pin "4") (pinfunction "CT_4") (pintype "passive"))
    )
    (net (code "55") (name "GND") (class "Default")
      (node (ref "C1") (pin "1") (pinfunction "1_1") (pintype "passive"))
      (node (ref "C12") (pin "1") (pinfunction "1_1") (pintype "passive"))
      (node (ref "C13") (pin "1") (pinfunction "1_1") (pintype "passive"))
      (node (ref "C14") (pin "1") (pinfunction "1_1") (pintype "passive"))
      (node (ref "C15") (pin "1") (pinfunction "1_1") (pintype "passive"))
      (node (ref "C16") (pin "1") (pinfunction "1_1") (pintype "passive"))
      (node (ref "C17") (pin "1") (pinfunction "1_1") (pintype "passive"))
      (node (ref "C18") (pin "1") (pinfunction "1_1") (pintype "passive"))
      (node (ref "C2") (pin "1") (pinfunction "1_1") (pintype "passive"))
      (node (ref "C3") (pin "1") (pinfunction "1_1") (pintype "passive"))
      (node (ref "C5") (pin "1") (pinfunction "1_1") (pintype "passive"))
      (node (ref "C8") (pin "1") (pinfunction "1_1") (pintype "passive"))
      (node (ref "C9") (pin "1") (pinfunction "1_1") (pintype "passive"))
      (node (ref "D11") (pin "1") (pinfunction "1_1") (pintype "passive"))
      (node (ref "D13") (pin "1") (pinfunction "1_1") (pintype "passive"))
      (node (ref "D14") (pin "1") (pinfunction "1_1") (pintype "passive"))
      (node (ref "D15") (pin "1") (pinfunction "1_1") (pintype "passive"))
      (node (ref "D2") (pin "1") (pinfunction "1_1") (pintype "passive"))
      (node (ref "D5") (pin "1") (pinfunction "1_1") (pintype "passive"))
      (node (ref "D6") (pin "1") (pinfunction "1_1") (pintype "passive"))
      (node (ref "D8") (pin "1") (pinfunction "1_1") (pintype "passive"))
      (node (ref "D9") (pin "1") (pinfunction "1_1") (pintype "passive"))
      (node (ref "J5") (pin "5") (pinfunction "GND_5") (pintype "passive"))
      (node (ref "J5") (pin "6") (pinfunction "GND_6") (pintype "passive"))
      (node (ref "J5") (pin "7") (pinfunction "GND_7") (pintype "passive"))
      (node (ref "J5") (pin "8") (pinfunction "GND_8") (pintype "passive"))
      (node (ref "J5") (pin "9") (pinfunction "GND_9") (pintype "passive"))
      (node (ref "L1") (pin "1") (pinfunction "GND_1") (pintype "passive"))
      (node (ref "Q1") (pin "2") (pinfunction "E_2") (pintype "passive"))
      (node (ref "Q2") (pin "2") (pinfunction "E_2") (pintype "passive"))
      (node (ref "Q3") (pin "2") (pinfunction "E_2") (pintype "passive"))
      (node (ref "Q4") (pin "2") (pinfunction "E_2") (pintype "passive"))
      (node (ref "Q5") (pin "2") (pinfunction "E_2") (pintype "passive"))
      (node (ref "R10") (pin "1") (pinfunction "1_1") (pintype "passive"))
      (node (ref "R11") (pin "1") (pinfunction "1_1") (pintype "passive"))
      (node (ref "R15") (pin "1") (pinfunction "1_1") (pintype "passive"))
      (node (ref "R18") (pin "1") (pinfunction "1_1") (pintype "passive"))
      (node (ref "R28") (pin "1") (pinfunction "1_1") (pintype "passive"))
      (node (ref "R30") (pin "1") (pinfunction "1_1") (pintype "passive"))
      (node (ref "R4") (pin "1") (pinfunction "1_1") (pintype "passive"))
      (node (ref "SW1") (pin "2") (pinfunction "2_2") (pintype "passive"))
      (node (ref "SW2") (pin "2") (pinfunction "2_2") (pintype "passive"))
      (node (ref "SW3") (pin "2") (pinfunction "2_2") (pintype "passive"))
      (node (ref "SW3") (pin "4") (pinfunction "4_4") (pintype "passive"))
      (node (ref "SW4") (pin "2") (pinfunction "2_2") (pintype "passive"))
      (node (ref "SW4") (pin "4") (pinfunction "4_4") (pintype "passive"))
      (node (ref "SW5") (pin "2") (pinfunction "2_2") (pintype "passive"))
      (node (ref "SW5") (pin "4") (pinfunction "4_4") (pintype "passive"))
      (node (ref "SW6") (pin "2") (pinfunction "2_2") (pintype "passive"))
      (node (ref "SW6") (pin "4") (pinfunction "4_4") (pintype "passive"))
      (node (ref "SW7") (pin "2") (pinfunction "2_2") (pintype "passive"))
      (node (ref "SW7") (pin "4") (pinfunction "4_4") (pintype "passive"))
      (node (ref "U2") (pin "1") (pinfunction "GND_1") (pintype "passive"))
      (node (ref "U2") (pin "15") (pinfunction "GND_15") (pintype "passive"))
      (node (ref "U2") (pin "38") (pinfunction "GND_38") (pintype "passive"))
      (node (ref "U2") (pin "39") (pinfunction "GND_39") (pintype "passive"))
      (node (ref "U5") (pin "1") (pinfunction "GND/ADJ_1") (pintype "passive"))
      (node (ref "U8") (pin "29") (pinfunction "PGND_29") (pintype "passive"))
    )
    (net (code "56") (name "Net-(D9-Pad2)") (class "Default")
      (node (ref "D9") (pin "2") (pinfunction "2_2") (pintype "passive"))
      (node (ref "R13") (pin "1") (pinfunction "1_1") (pintype "passive"))
    )
    (net (code "57") (name "Net-(Q1-B)") (class "Default")
      (node (ref "Q1") (pin "1") (pinfunction "B_1") (pintype "passive"))
      (node (ref "R3") (pin "2") (pinfunction "2_2") (pintype "passive"))
      (node (ref "R4") (pin "2") (pinfunction "2_2") (pintype "passive"))
    )
    (net (code "58") (name "Net-(Q1-C)") (class "Default")
      (node (ref "D1") (pin "A") (pinfunction "A_A") (pintype "passive"))
      (node (ref "Q1") (pin "3") (pinfunction "C_3") (pintype "passive"))
      (node (ref "RL1") (pin "4") (pinfunction "4_4") (pintype "passive"))
    )
    (net (code "59") (name "Net-(Q2-B)") (class "Default")
      (node (ref "Q2") (pin "1") (pinfunction "B_1") (pintype "passive"))
      (node (ref "R10") (pin "2") (pinfunction "2_2") (pintype "passive"))
      (node (ref "R8") (pin "2") (pinfunction "2_2") (pintype "passive"))
    )
    (net (code "60") (name "Net-(Q2-C)") (class "Default")
      (node (ref "D3") (pin "A") (pinfunction "A_A") (pintype "passive"))
      (node (ref "Q2") (pin "3") (pinfunction "C_3") (pintype "passive"))
      (node (ref "RL2") (pin "4") (pinfunction "4_4") (pintype "passive"))
    )
    (net (code "61") (name "Net-(Q3-B)") (class "Default")
      (node (ref "Q3") (pin "1") (pinfunction "B_1") (pintype "passive"))
      (node (ref "R11") (pin "2") (pinfunction "2_2") (pintype "passive"))
      (node (ref "R9") (pin "2") (pinfunction "2_2") (pintype "passive"))
    )
    (net (code "62") (name "Net-(Q3-C)") (class "Default")
      (node (ref "D4") (pin "A") (pinfunction "A_A") (pintype "passive"))
      (node (ref "Q3") (pin "3") (pinfunction "C_3") (pintype "passive"))
      (node (ref "RL3") (pin "4") (pinfunction "4_4") (pintype "passive"))
    )
    (net (code "63") (name "Net-(Q4-B)") (class "Default")
      (node (ref "Q4") (pin "1") (pinfunction "B_1") (pintype "passive"))
      (node (ref "R14") (pin "2") (pinfunction "2_2") (pintype "passive"))
      (node (ref "R15") (pin "2") (pinfunction "2_2") (pintype "passive"))
    )
    (net (code "64") (name "Net-(Q4-C)") (class "Default")
      (node (ref "D7") (pin "A") (pinfunction "A_A") (pintype "passive"))
      (node (ref "Q4") (pin "3") (pinfunction "C_3") (pintype "passive"))
      (node (ref "RL4") (pin "4") (pinfunction "4_4") (pintype "passive"))
    )
    (net (code "65") (name "Net-(Q5-B)") (class "Default")
      (node (ref "Q5") (pin "1") (pinfunction "B_1") (pintype "passive"))
      (node (ref "R17") (pin "2") (pinfunction "2_2") (pintype "passive"))
      (node (ref "R18") (pin "2") (pinfunction "2_2") (pintype "passive"))
    )
    (net (code "66") (name "Net-(Q5-C)") (class "Default")
      (node (ref "D10") (pin "A") (pinfunction "A_A") (pintype "passive"))
      (node (ref "Q5") (pin "3") (pinfunction "C_3") (pintype "passive"))
      (node (ref "RL5") (pin "4") (pinfunction "4_4") (pintype "passive"))
    )
    (net (code "67") (name "Net-(Q6-B)") (class "Default")
      (node (ref "Q6") (pin "1") (pinfunction "B_1") (pintype "passive"))
      (node (ref "R27") (pin "2") (pinfunction "2_2") (pintype "passive"))
    )
    (net (code "68") (name "Net-(Q7-B)") (class "Default")
      (node (ref "Q7") (pin "1") (pinfunction "B_1") (pintype "passive"))
      (node (ref "R31") (pin "2") (pinfunction "2_2") (pintype "passive"))
    )
    (net (code "69") (name "Net-(R30-Pad2)") (class "Default")
      (node (ref "R30") (pin "2") (pinfunction "2_2") (pintype "passive"))
      (node (ref "U8") (pin "11") (pinfunction "SUSPEND_11") (pintype "passive"))
    )
    (net (code "70") (name "Net-(U1-A)") (class "Default")
      (node (ref "R2") (pin "2") (pinfunction "2_2") (pintype "passive"))
      (node (ref "U1") (pin "1") (pinfunction "A_1") (pintype "passive"))
    )
    (net (code "71") (name "Net-(U1-C)") (class "Default")
      (node (ref "D2") (pin "2") (pinfunction "2_2") (pintype "passive"))
      (node (ref "U1") (pin "2") (pinfunction "C_2") (pintype "passive"))
    )
    (net (code "72") (name "Net-(U1-ET)") (class "Default")
      (node (ref "R3") (pin "1") (pinfunction "1_1") (pintype "passive"))
      (node (ref "U1") (pin "3") (pinfunction "ET_3") (pintype "passive"))
    )
    (net (code "73") (name "Net-(U3-A)") (class "Default")
      (node (ref "R6") (pin "2") (pinfunction "2_2") (pintype "passive"))
      (node (ref "U3") (pin "1") (pinfunction "A_1") (pintype "passive"))
    )
    (net (code "74") (name "Net-(U3-C)") (class "Default")
      (node (ref "D5") (pin "2") (pinfunction "2_2") (pintype "passive"))
      (node (ref "U3") (pin "2") (pinfunction "C_2") (pintype "passive"))
    )
    (net (code "75") (name "Net-(U3-ET)") (class "Default")
      (node (ref "R8") (pin "1") (pinfunction "1_1") (pintype "passive"))
      (node (ref "U3") (pin "3") (pinfunction "ET_3") (pintype "passive"))
    )
    (net (code "76") (name "Net-(U4-A)") (class "Default")
      (node (ref "R7") (pin "2") (pinfunction "2_2") (pintype "passive"))
      (node (ref "U4") (pin "1") (pinfunction "A_1") (pintype "passive"))
    )
    (net (code "77") (name "Net-(U4-C)") (class "Default")
      (node (ref "D6") (pin "2") (pinfunction "2_2") (pintype "passive"))
      (node (ref "U4") (pin "2") (pinfunction "C_2") (pintype "passive"))
    )
    (net (code "78") (name "Net-(U4-ET)") (class "Default")
      (node (ref "R9") (pin "1") (pinfunction "1_1") (pintype "passive"))
      (node (ref "U4") (pin "3") (pinfunction "ET_3") (pintype "passive"))
    )
    (net (code "79") (name "Net-(U6-A)") (class "Default")
      (node (ref "R12") (pin "2") (pinfunction "2_2") (pintype "passive"))
      (node (ref "U6") (pin "1") (pinfunction "A_1") (pintype "passive"))
    )
    (net (code "80") (name "Net-(U6-C)") (class "Default")
      (node (ref "D8") (pin "2") (pinfunction "2_2") (pintype "passive"))
      (node (ref "U6") (pin "2") (pinfunction "C_2") (pintype "passive"))
    )
    (net (code "81") (name "Net-(U6-ET)") (class "Default")
      (node (ref "R14") (pin "1") (pinfunction "1_1") (pintype "passive"))
      (node (ref "U6") (pin "3") (pinfunction "ET_3") (pintype "passive"))
    )
    (net (code "82") (name "Net-(U7-A)") (class "Default")
      (node (ref "R16") (pin "2") (pinfunction "2_2") (pintype "passive"))
      (node (ref "U7") (pin "1") (pinfunction "A_1") (pintype "passive"))
    )
    (net (code "83") (name "Net-(U7-C)") (class "Default")
      (node (ref "D11") (pin "2") (pinfunction "2_2") (pintype "passive"))
      (node (ref "U7") (pin "2") (pinfunction "C_2") (pintype "passive"))
    )
    (net (code "84") (name "Net-(U7-ET)") (class "Default")
      (node (ref "R17") (pin "1") (pinfunction "1_1") (pintype "passive"))
      (node (ref "U7") (pin "3") (pinfunction "ET_3") (pintype "passive"))
    )
    (net (code "85") (name "Net-(U8-RST)") (class "Default")
      (node (ref "R29") (pin "2") (pinfunction "2_2") (pintype "passive"))
      (node (ref "U8") (pin "9") (pinfunction "RST_9") (pintype "passive"))
    )
    (net (code "86") (name "Net-(U8-VBUS)") (class "Default")
      (node (ref "R26") (pin "2") (pinfunction "2_2") (pintype "passive"))
      (node (ref "R28") (pin "2") (pinfunction "2_2") (pintype "passive"))
      (node (ref "U8") (pin "8") (pinfunction "VBUS_8") (pintype "passive"))
    )
    (net (code "87") (name "VBUS") (class "Default")
      (node (ref "D12") (pin "A") (pinfunction "A_A") (pintype "passive"))
      (node (ref "D13") (pin "2") (pinfunction "2_2") (pintype "passive"))
      (node (ref "J5") (pin "1") (pinfunction "VBUS_1") (pintype "passive"))
      (node (ref "R26") (pin "1") (pinfunction "1_1") (pintype "passive"))
    )
    (net (code "88") (name "unconnected-(J1-Pad1)") (class "Default")
      (node (ref "J1") (pin "1") (pinfunction "1_1") (pintype "passive"))
    )
    (net (code "89") (name "unconnected-(J2-Pad1)") (class "Default")
      (node (ref "J2") (pin "1") (pinfunction "1_1") (pintype "passive"))
    )
    (net (code "90") (name "unconnected-(J3-Pad1)") (class "Default")
      (node (ref "J3") (pin "1") (pinfunction "1_1") (pintype "passive"))
    )
    (net (code "91") (name "unconnected-(J4-Pad1)") (class "Default")
      (node (ref "J4") (pin "1") (pinfunction "1_1") (pintype "passive"))
    )
    (net (code "92") (name "unconnected-(J5-NC-Pad4)") (class "Default")
      (node (ref "J5") (pin "4") (pinfunction "NC_4") (pintype "passive"))
    )
    (net (code "93") (name "unconnected-(RL1-Pad2)") (class "Default")
      (node (ref "RL1") (pin "2") (pinfunction "2_2") (pintype "passive"))
    )
    (net (code "94") (name "unconnected-(RL2-Pad2)") (class "Default")
      (node (ref "RL2") (pin "2") (pinfunction "2_2") (pintype "passive"))
    )
    (net (code "95") (name "unconnected-(RL3-Pad2)") (class "Default")
      (node (ref "RL3") (pin "2") (pinfunction "2_2") (pintype "passive"))
    )
    (net (code "96") (name "unconnected-(RL4-Pad2)") (class "Default")
      (node (ref "RL4") (pin "2") (pinfunction "2_2") (pintype "passive"))
    )
    (net (code "97") (name "unconnected-(RL5-Pad2)") (class "Default")
      (node (ref "RL5") (pin "2") (pinfunction "2_2") (pintype "passive"))
    )
    (net (code "98") (name "unconnected-(U8-DCD-Pad1)") (class "Default")
      (node (ref "U8") (pin "1") (pinfunction "DCD_1") (pintype "passive"))
    )
    (net (code "99") (name "unconnected-(U8-GND-Pad3)") (class "Default")
      (node (ref "U8") (pin "3") (pinfunction "GND_3") (pintype "passive"))
    )
    (net (code "100") (name "unconnected-(U8-NC1-Pad10)") (class "Default")
      (node (ref "U8") (pin "10") (pinfunction "NC1_10") (pintype "passive"))
    )
    (net (code "101") (name "unconnected-(U8-NC2-Pad13)") (class "Default")
      (node (ref "U8") (pin "13") (pinfunction "NC2_13") (pintype "passive"))
    )
    (net (code "102") (name "unconnected-(U8-NC3-Pad14)") (class "Default")
      (node (ref "U8") (pin "14") (pinfunction "NC3_14") (pintype "passive"))
    )
    (net (code "103") (name "unconnected-(U8-NC4-Pad15)") (class "Default")
      (node (ref "U8") (pin "15") (pinfunction "NC4_15") (pintype "passive"))
    )
    (net (code "104") (name "unconnected-(U8-NC5-Pad16)") (class "Default")
      (node (ref "U8") (pin "16") (pinfunction "NC5_16") (pintype "passive"))
    )
    (net (code "105") (name "unconnected-(U8-NC6-Pad17)") (class "Default")
      (node (ref "U8") (pin "17") (pinfunction "NC6_17") (pintype "passive"))
    )
    (net (code "106") (name "unconnected-(U8-NC7-Pad18)") (class "Default")
      (node (ref "U8") (pin "18") (pinfunction "NC7_18") (pintype "passive"))
    )
    (net (code "107") (name "unconnected-(U8-NC8-Pad19)") (class "Default")
      (node (ref "U8") (pin "19") (pinfunction "NC8_19") (pintype "passive"))
    )
    (net (code "108") (name "unconnected-(U8-NC9-Pad20)") (class "Default")
      (node (ref "U8") (pin "20") (pinfunction "NC9_20") (pintype "passive"))
    )
    (net (code "109") (name "unconnected-(U8-NC10-Pad21)") (class "Default")
      (node (ref "U8") (pin "21") (pinfunction "NC10_21") (pintype "passive"))
    )
    (net (code "110") (name "unconnected-(U8-NC11-Pad22)") (class "Default")
      (node (ref "U8") (pin "22") (pinfunction "NC11_22") (pintype "passive"))
    )
    (net (code "111") (name "unconnected-(U8-RI-Pad2)") (class "Default")
      (node (ref "U8") (pin "2") (pinfunction "RI_2") (pintype "passive"))
    )
    (net (code "112") (name "unconnected-(U8-SUSPEND-Pad12)") (class "Default")
      (node (ref "U8") (pin "12") (pinfunction "SUSPEND_12") (pintype "passive"))
    )
  )
)
